# 02_Top_Level.net
KiCad netlist of a schematic drawn in Altium Designer
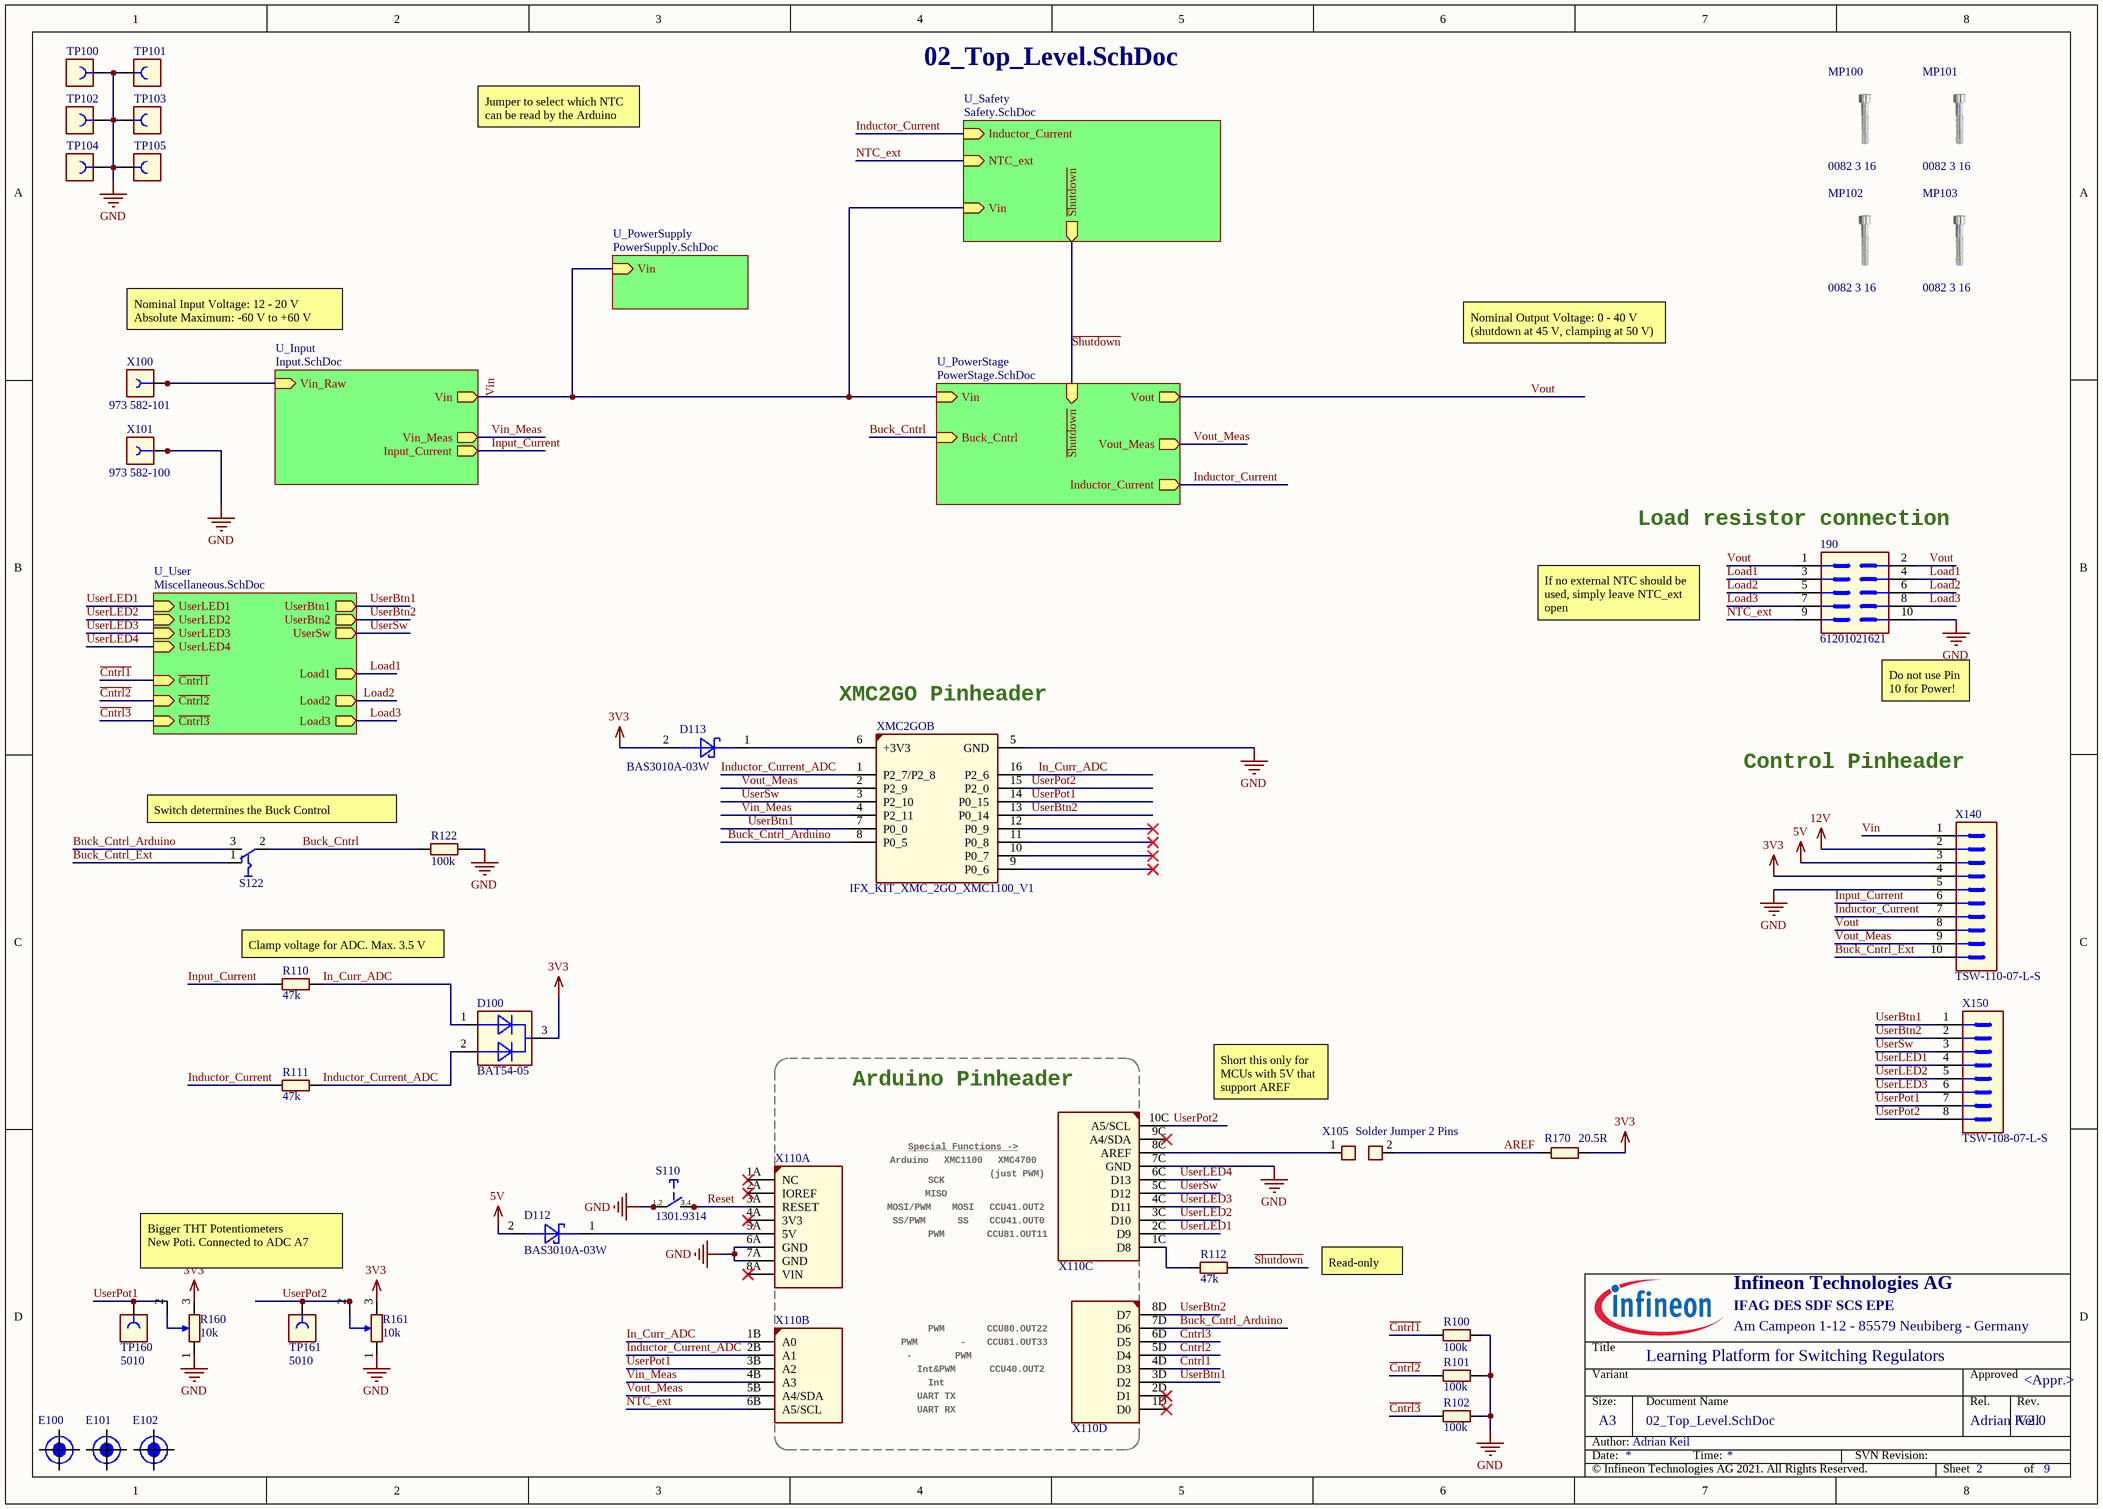
[diagram p0: 02_Top_Level.SchDoc]

(export (version "E")
  (design (tool "Eeschema 10.0.6"))
  (components
    (comp (ref "190")
      (value "61201021621")
      (footprint "CON-M-THT-61201021621")
      (description "WR-BHD Male Box Header, 2.54mm pitch, 10 pin, Vertical, Double row")
      (fields (field (name "MANUFACTURER") "Wurth Elektronik"))
      (libsource (lib "PCBLibraryData") (part "Header 5X2"))
    )
    (comp (ref "D100")
      (value "BAT54-05")
      (footprint "SOT95P240X110-3N-1-V")
      (description "Silicon Schottky Diode, LS(nH) 1.8, VR 30V")
      (fields
        (field (name "LEGACY PARTNUMBER") "IFX01401370")
        (field (name "MANUFACTURER") "Infineon Technologies")
      )
      (libsource (lib "PCBLibraryData") (part "d_dual_a1a2c3_3p"))
    )
    (comp (ref "D112")
      (value "BAS3010A-03W")
      (footprint "SOD2513X110N")
      (description "Medium Power AF Schottky Diode")
      (fields
        (field (name "LEGACY PARTNUMBER") "IFX01400145")
        (field (name "MANUFACTURER") "Infineon Technologies")
      )
      (libsource (lib "PCBLibraryData") (part "d_schottky_a"))
    )
    (comp (ref "D113")
      (value "BAS3010A-03W")
      (footprint "SOD2513X110N")
      (description "Medium Power AF Schottky Diode")
      (fields
        (field (name "LEGACY PARTNUMBER") "IFX01400145")
        (field (name "MANUFACTURER") "Infineon Technologies")
      )
      (libsource (lib "PCBLibraryData") (part "d_schottky_a"))
    )
    (comp (ref "E100")
      (value "~")
      (footprint "fiducial")
      (description "Fiducial Mark")
      (fields
        (field (name "LEGACY PARTNUMBER") "MEC10000008")
        (field (name "MANUFACTURER") "Infineon Technologies")
      )
      (libsource (lib "PCBLibraryData") (part "fiducial"))
    )
    (comp (ref "E101")
      (value "~")
      (footprint "fiducial")
      (description "Fiducial Mark")
      (fields
        (field (name "LEGACY PARTNUMBER") "MEC10000008")
        (field (name "MANUFACTURER") "Infineon Technologies")
      )
      (libsource (lib "PCBLibraryData") (part "fiducial"))
    )
    (comp (ref "E102")
      (value "~")
      (footprint "fiducial")
      (description "Fiducial Mark")
      (fields
        (field (name "LEGACY PARTNUMBER") "MEC10000008")
        (field (name "MANUFACTURER") "Infineon Technologies")
      )
      (libsource (lib "PCBLibraryData") (part "fiducial"))
    )
    (comp (ref "MP100")
      (value "0082 3 16")
      (footprint "SCREW_0082 3 16_NPTH")
      (description "Cheese Head Screw With Hexagon Socket, DIN 912 (ISO 4762), M3, 16mm length")
      (fields
        (field (name "LEGACY PARTNUMBER") "MEC10000167")
        (field (name "MANUFACTURER") "Wurth Elektronik")
      )
      (libsource (lib "PCBLibraryData") (part "Screw_0082 3 16"))
    )
    (comp (ref "MP101")
      (value "0082 3 16")
      (footprint "SCREW_0082 3 16_NPTH")
      (description "Cheese Head Screw With Hexagon Socket, DIN 912 (ISO 4762), M3, 16mm length")
      (fields
        (field (name "LEGACY PARTNUMBER") "MEC10000167")
        (field (name "MANUFACTURER") "Wurth Elektronik")
      )
      (libsource (lib "PCBLibraryData") (part "Screw_0082 3 16"))
    )
    (comp (ref "MP102")
      (value "0082 3 16")
      (footprint "SCREW_0082 3 16_NPTH")
      (description "Cheese Head Screw With Hexagon Socket, DIN 912 (ISO 4762), M3, 16mm length")
      (fields
        (field (name "LEGACY PARTNUMBER") "MEC10000167")
        (field (name "MANUFACTURER") "Wurth Elektronik")
      )
      (libsource (lib "PCBLibraryData") (part "Screw_0082 3 16"))
    )
    (comp (ref "MP103")
      (value "0082 3 16")
      (footprint "SCREW_0082 3 16_NPTH")
      (description "Cheese Head Screw With Hexagon Socket, DIN 912 (ISO 4762), M3, 16mm length")
      (fields
        (field (name "LEGACY PARTNUMBER") "MEC10000167")
        (field (name "MANUFACTURER") "Wurth Elektronik")
      )
      (libsource (lib "PCBLibraryData") (part "Screw_0082 3 16"))
    )
    (comp (ref "R100")
      (value "100k")
      (footprint "RESC3216X60N")
      (description "RES / STD / 100k / 250mW / 1% / 100ppm/K / -55°C to 155°C / 1206(3216) / SMD / -")
      (fields (field (name "LEGACY PARTNUMBER") "RES01802971") (field (name "MANUFACTURER") "Vishay"))
      (libsource (lib "") (part "RES-SGL-STD-02P_00000006_1"))
    )
    (comp (ref "R101")
      (value "100k")
      (footprint "RESC3216X60N")
      (description "RES / STD / 100k / 250mW / 1% / 100ppm/K / -55°C to 155°C / 1206(3216) / SMD / -")
      (fields (field (name "LEGACY PARTNUMBER") "RES01802971") (field (name "MANUFACTURER") "Vishay"))
      (libsource (lib "") (part "RES-SGL-STD-02P_00000006_1"))
    )
    (comp (ref "R102")
      (value "100k")
      (footprint "RESC3216X60N")
      (description "RES / STD / 100k / 250mW / 1% / 100ppm/K / -55°C to 155°C / 1206(3216) / SMD / -")
      (fields (field (name "LEGACY PARTNUMBER") "RES01802971") (field (name "MANUFACTURER") "Vishay"))
      (libsource (lib "") (part "RES-SGL-STD-02P_00000006_1"))
    )
    (comp (ref "R110")
      (value "47k")
      (footprint "RESC3216X60N")
      (description "RES / STD / 47k / 250mW / 1% / 100ppm/K / -55°C to 155°C / 1206(3216) / SMD / -")
      (fields (field (name "LEGACY PARTNUMBER") "RES01802933") (field (name "MANUFACTURER") "Vishay"))
      (libsource (lib "PCBLibraryData") (part "RES-SGL-STD-02P_00000006"))
    )
    (comp (ref "R111")
      (value "47k")
      (footprint "RESC3216X60N")
      (description "RES / STD / 47k / 250mW / 1% / 100ppm/K / -55°C to 155°C / 1206(3216) / SMD / -")
      (fields (field (name "LEGACY PARTNUMBER") "RES01802933") (field (name "MANUFACTURER") "Vishay"))
      (libsource (lib "PCBLibraryData") (part "RES-SGL-STD-02P_00000006"))
    )
    (comp (ref "R112")
      (value "47k")
      (footprint "RESC3216X60N")
      (description "RES / STD / 47k / 250mW / 1% / 100ppm/K / -55°C to 155°C / 1206(3216) / SMD / -")
      (fields (field (name "LEGACY PARTNUMBER") "RES01802933") (field (name "MANUFACTURER") "Vishay"))
      (libsource (lib "PCBLibraryData") (part "RES-SGL-STD-02P_00000006"))
    )
    (comp (ref "R122")
      (value "100k")
      (footprint "RESC3216X60N")
      (description "RES / STD / 100k / 250mW / 1% / 100ppm/K / -55°C to 155°C / 1206(3216) / SMD / -")
      (fields (field (name "LEGACY PARTNUMBER") "RES01802971") (field (name "MANUFACTURER") "Vishay"))
      (libsource (lib "") (part "RES-SGL-STD-02P_00000006_1"))
    )
    (comp (ref "R160")
      (value "10k")
      (footprint "POT-THT-3362P")
      (fields (field (name "MANUFACTURER") "Bourns"))
      (libsource (lib "PCBLibraryData") (part "RES-SGL-VAR-03P_00000026"))
    )
    (comp (ref "R161")
      (value "10k")
      (footprint "POT-THT-3362P")
      (fields (field (name "MANUFACTURER") "Bourns"))
      (libsource (lib "PCBLibraryData") (part "RES-SGL-VAR-03P_00000026"))
    )
    (comp (ref "R170")
      (value "20.5R")
      (footprint "RESC3216X60N")
      (description "RES / STD / 20.5R / 250mW / 1% / 100ppm/K / -55°C to 155°C / 1206(3216) / SMD / -")
      (fields (field (name "LEGACY PARTNUMBER") "RES01802548") (field (name "MANUFACTURER") "Vishay"))
      (libsource (lib "") (part "RES-SGL-STD-02P_00000006_1"))
    )
    (comp (ref "S110")
      (value "1301.9314")
      (footprint "SW-SMD-1301.9314")
      (description "Pushbutton Tactile Switch, Single Pole Single Throw, 4 Pins")
      (fields (field (name "LEGACY PARTNUMBER") "CON01500305") (field (name "MANUFACTURER") "Schurter"))
      (libsource (lib "PCBLibraryData") (part "sw_sr_no12_34_4p"))
    )
    (comp (ref "S122")
      (value "CL-SB-12A-01T")
      (footprint "SW-SMD-CL-SB-12A-01T")
      (description "Slid Switch, 12V, 200mA")
      (fields (field (name "MANUFACTURER") "NIDEC COPAL ELECTRONICS, Inc."))
      (libsource (lib "PCBLibraryData") (part "sw_co213_3p"))
    )
    (comp (ref "TP100")
      (value "5011")
      (footprint "CON-THT-TP-5011")
      (description "PC Test Point-Multipurpose THT, Black")
      (fields
        (field (name "LEGACY PARTNUMBER") "CON01500530")
        (field (name "MANUFACTURER") "Keystone Electronics Corp.")
      )
      (libsource (lib "PCBLibraryData") (part "connector_1_f"))
    )
    (comp (ref "TP101")
      (value "5011")
      (footprint "CON-THT-TP-5011")
      (description "PC Test Point-Multipurpose THT, Black")
      (fields
        (field (name "LEGACY PARTNUMBER") "CON01500530")
        (field (name "MANUFACTURER") "Keystone Electronics Corp.")
      )
      (libsource (lib "") (part "connector_1_f_2"))
    )
    (comp (ref "TP102")
      (value "5011")
      (footprint "CON-THT-TP-5011")
      (description "PC Test Point-Multipurpose THT, Black")
      (fields
        (field (name "LEGACY PARTNUMBER") "CON01500530")
        (field (name "MANUFACTURER") "Keystone Electronics Corp.")
      )
      (libsource (lib "PCBLibraryData") (part "connector_1_f"))
    )
    (comp (ref "TP103")
      (value "5011")
      (footprint "CON-THT-TP-5011")
      (description "PC Test Point-Multipurpose THT, Black")
      (fields
        (field (name "LEGACY PARTNUMBER") "CON01500530")
        (field (name "MANUFACTURER") "Keystone Electronics Corp.")
      )
      (libsource (lib "") (part "connector_1_f_2"))
    )
    (comp (ref "TP104")
      (value "5011")
      (footprint "CON-THT-TP-5011")
      (description "PC Test Point-Multipurpose THT, Black")
      (fields
        (field (name "LEGACY PARTNUMBER") "CON01500530")
        (field (name "MANUFACTURER") "Keystone Electronics Corp.")
      )
      (libsource (lib "PCBLibraryData") (part "connector_1_f"))
    )
    (comp (ref "TP105")
      (value "5011")
      (footprint "CON-THT-TP-5011")
      (description "PC Test Point-Multipurpose THT, Black")
      (fields
        (field (name "LEGACY PARTNUMBER") "CON01500530")
        (field (name "MANUFACTURER") "Keystone Electronics Corp.")
      )
      (libsource (lib "") (part "connector_1_f_2"))
    )
    (comp (ref "TP160")
      (value "5010")
      (footprint "CON-THT-TP-5010")
      (description "PC Test Point-Multipurpose THT, Red")
      (fields
        (field (name "LEGACY PARTNUMBER") "CON01500529")
        (field (name "MANUFACTURER") "Keystone Electronics Corp.")
      )
      (libsource (lib "") (part "connector_1_f_1"))
    )
    (comp (ref "TP161")
      (value "5010")
      (footprint "CON-THT-TP-5010")
      (description "PC Test Point-Multipurpose THT, Red")
      (fields
        (field (name "LEGACY PARTNUMBER") "CON01500529")
        (field (name "MANUFACTURER") "Keystone Electronics Corp.")
      )
      (libsource (lib "") (part "connector_1_f_1"))
    )
    (comp (ref "X100")
      (value "973 582-101")
      (footprint "CON-THT-973 582- 101")
      (description "Banana Socket, Red, 17.5mm Pitch")
      (fields
        (field (name "LEGACY PARTNUMBER") "CON01500041")
        (field (name "MANUFACTURER") "Hirschmann Test & Measurement")
      )
      (libsource (lib "PCBLibraryData") (part "soc_banana_2p"))
    )
    (comp (ref "X101")
      (value "973 582-100")
      (footprint "CON-THT-973 582- 100")
      (description "Banana Socket, black, 17.5mm Pitch")
      (fields
        (field (name "LEGACY PARTNUMBER") "CON01500045")
        (field (name "MANUFACTURER") "Hirschmann Test & Measurement")
      )
      (libsource (lib "PCBLibraryData") (part "soc_banana_2p"))
    )
    (comp (ref "X105")
      (value "Solder Jumper 2 Pins")
      (footprint "SOLDER_BRIDGE_0.7X1.299PAD")
      (fields
        (field (name "LEGACY PARTNUMBER") "CON01500959")
        (field (name "MANUFACTURER") "Infineon Technologies")
      )
      (libsource (lib "PCBLibraryData") (part "SJP_2P"))
    )
    (comp (ref "X110")
      (value "Arduino-Uno")
      (footprint "Arduino-Uno")
      (description "Arduino Uno is a microcontroller board based on the ATmega328P")
      (fields (field (name "MANUFACTURER") "Infineon Technologies"))
      (libsource (lib "") (part "Arduino-Uno_1"))
    )
    (comp (ref "X140")
      (value "TSW-110-07-L-S")
      (footprint "CON-M-THT-TSW-110-07-L-S")
      (description "Through hole .025 SQ Post Header, 2.54mm pitch, 10 pin, vertical, single row")
      (fields (field (name "LEGACY PARTNUMBER") "CON01500578") (field (name "MANUFACTURER") "Samtec"))
      (libsource (lib "PCBLibraryData") (part "Header 10"))
    )
    (comp (ref "X150")
      (value "TSW-108-07-L-S")
      (footprint "CON-M-THT-TSW-108-07-L-S")
      (description "Through hole .025 SQ Post Header, 2.54mm pitch, 8 pin, vertical, single row")
      (fields (field (name "LEGACY PARTNUMBER") "CON01500577") (field (name "MANUFACTURER") "Samtec"))
      (libsource (lib "PCBLibraryData") (part "Header 8"))
    )
    (comp (ref "XMC2GO")
      (value "IFX_KIT_XMC_2GO_XMC1100_V1")
      (footprint "IFX-THT-KIT_XMC_2GO_XMC1100_V1")
      (description "Evaluation Board For XMC1000 Family, The XMC 2Go, 16 Pins+5 Pins")
      (fields (field (name "MANUFACTURER") "Infineon Technologies"))
      (libsource (lib "PCBLibraryData") (part "KIT_XMC_2GO_XMC1100_V1"))
    )
  )
  (nets
    (net (code "1") (name "/AREF") (class "Default")
      (node (ref "R170") (pin "1") (pinfunction "1_1") (pintype "passive"))
      (node (ref "X105") (pin "2") (pinfunction "2_2") (pintype "passive"))
    )
    (net (code "2") (name "/Buck_Cntrl") (class "Default")
      (node (ref "R122") (pin "1") (pinfunction "1_1") (pintype "passive"))
      (node (ref "S122") (pin "2") (pinfunction "2_2") (pintype "passive"))
    )
    (net (code "3") (name "/Buck_Cntrl_Arduino") (class "Default")
      (node (ref "S122") (pin "3") (pinfunction "3_3") (pintype "passive"))
      (node (ref "X110") (pin "7D") (pinfunction "D6_7D") (pintype "passive"))
      (node (ref "XMC2GO") (pin "8") (pinfunction "P0_5_8") (pintype "passive"))
    )
    (net (code "4") (name "/Buck_Cntrl_Ext") (class "Default")
      (node (ref "S122") (pin "1") (pinfunction "1_1") (pintype "passive"))
      (node (ref "X140") (pin "10") (pinfunction "10_10") (pintype "passive"))
    )
    (net (code "5") (name "/Cntrl1") (class "Default")
      (node (ref "R100") (pin "1") (pinfunction "1_1") (pintype "passive"))
      (node (ref "X110") (pin "4D") (pinfunction "D3_4D") (pintype "passive"))
    )
    (net (code "6") (name "/Cntrl2") (class "Default")
      (node (ref "R101") (pin "1") (pinfunction "1_1") (pintype "passive"))
      (node (ref "X110") (pin "5D") (pinfunction "D4_5D") (pintype "passive"))
    )
    (net (code "7") (name "/Cntrl3") (class "Default")
      (node (ref "R102") (pin "1") (pinfunction "1_1") (pintype "passive"))
      (node (ref "X110") (pin "6D") (pinfunction "D5_6D") (pintype "passive"))
    )
    (net (code "8") (name "/In_Curr_ADC") (class "Default")
      (node (ref "D100") (pin "1") (pinfunction "ANODE_1_1") (pintype "passive"))
      (node (ref "R110") (pin "1") (pinfunction "1_1") (pintype "passive"))
      (node (ref "X110") (pin "1B") (pinfunction "A0_1B") (pintype "passive"))
      (node (ref "XMC2GO") (pin "16") (pinfunction "P2_6_16") (pintype "passive"))
    )
    (net (code "9") (name "/Inductor_Current") (class "Default")
      (node (ref "R111") (pin "2") (pinfunction "2_2") (pintype "passive"))
      (node (ref "X140") (pin "7") (pinfunction "7_7") (pintype "passive"))
    )
    (net (code "10") (name "/Inductor_Current_ADC") (class "Default")
      (node (ref "D100") (pin "2") (pinfunction "ANODE_2_2") (pintype "passive"))
      (node (ref "R111") (pin "1") (pinfunction "1_1") (pintype "passive"))
      (node (ref "X110") (pin "2B") (pinfunction "A1_2B") (pintype "passive"))
      (node (ref "XMC2GO") (pin "1") (pinfunction "P2_7/P2_8_1") (pintype "passive"))
    )
    (net (code "11") (name "/Input_Current") (class "Default")
      (node (ref "R110") (pin "2") (pinfunction "2_2") (pintype "passive"))
      (node (ref "X140") (pin "6") (pinfunction "6_6") (pintype "passive"))
    )
    (net (code "12") (name "/Load1") (class "Default")
      (node (ref "190") (pin "3") (pinfunction "3_3") (pintype "passive"))
      (node (ref "190") (pin "4") (pinfunction "4_4") (pintype "passive"))
    )
    (net (code "13") (name "/Load2") (class "Default")
      (node (ref "190") (pin "5") (pinfunction "5_5") (pintype "passive"))
      (node (ref "190") (pin "6") (pinfunction "6_6") (pintype "passive"))
    )
    (net (code "14") (name "/Load3") (class "Default")
      (node (ref "190") (pin "7") (pinfunction "7_7") (pintype "passive"))
      (node (ref "190") (pin "8") (pinfunction "8_8") (pintype "passive"))
    )
    (net (code "15") (name "/NTC_ext") (class "Default")
      (node (ref "190") (pin "9") (pinfunction "9_9") (pintype "passive"))
      (node (ref "X110") (pin "6B") (pinfunction "A5/SCL_6B") (pintype "passive"))
    )
    (net (code "16") (name "/Reset") (class "Default")
      (node (ref "S110") (pin "3") (pinfunction "3_3") (pintype "passive"))
      (node (ref "S110") (pin "4") (pinfunction "4_4") (pintype "passive"))
      (node (ref "X110") (pin "3A") (pinfunction "RESET_3A") (pintype "passive"))
    )
    (net (code "17") (name "/Shutdown") (class "Default")
      (node (ref "R112") (pin "1") (pinfunction "1_1") (pintype "passive"))
    )
    (net (code "18") (name "/UserBtn1") (class "Default")
      (node (ref "X110") (pin "3D") (pinfunction "D2_3D") (pintype "passive"))
      (node (ref "X150") (pin "1") (pinfunction "1_1") (pintype "passive"))
      (node (ref "XMC2GO") (pin "7") (pinfunction "P0_0_7") (pintype "passive"))
    )
    (net (code "19") (name "/UserBtn2") (class "Default")
      (node (ref "X110") (pin "8D") (pinfunction "D7_8D") (pintype "passive"))
      (node (ref "X150") (pin "2") (pinfunction "2_2") (pintype "passive"))
      (node (ref "XMC2GO") (pin "13") (pinfunction "P0_14_13") (pintype "passive"))
    )
    (net (code "20") (name "/UserLED1") (class "Default")
      (node (ref "X110") (pin "2C") (pinfunction "D9_2C") (pintype "passive"))
      (node (ref "X150") (pin "4") (pinfunction "4_4") (pintype "passive"))
    )
    (net (code "21") (name "/UserLED2") (class "Default")
      (node (ref "X110") (pin "3C") (pinfunction "D10_3C") (pintype "passive"))
      (node (ref "X150") (pin "5") (pinfunction "5_5") (pintype "passive"))
    )
    (net (code "22") (name "/UserLED3") (class "Default")
      (node (ref "X110") (pin "4C") (pinfunction "D11_4C") (pintype "passive"))
      (node (ref "X150") (pin "6") (pinfunction "6_6") (pintype "passive"))
    )
    (net (code "23") (name "/UserLED4") (class "Default")
      (node (ref "X110") (pin "6C") (pinfunction "D13_6C") (pintype "passive"))
    )
    (net (code "24") (name "/UserPot1") (class "Default")
      (node (ref "R160") (pin "2") (pinfunction "2_2") (pintype "passive"))
      (node (ref "TP160") (pin "1") (pinfunction "1_1") (pintype "passive"))
      (node (ref "X110") (pin "3B") (pinfunction "A2_3B") (pintype "passive"))
      (node (ref "X150") (pin "7") (pinfunction "7_7") (pintype "passive"))
      (node (ref "XMC2GO") (pin "14") (pinfunction "P0_15_14") (pintype "passive"))
    )
    (net (code "25") (name "/UserPot2") (class "Default")
      (node (ref "R161") (pin "2") (pinfunction "2_2") (pintype "passive"))
      (node (ref "TP161") (pin "1") (pinfunction "1_1") (pintype "passive"))
      (node (ref "X110") (pin "10C") (pinfunction "A5/SCL_10C") (pintype "passive"))
      (node (ref "X150") (pin "8") (pinfunction "8_8") (pintype "passive"))
      (node (ref "XMC2GO") (pin "15") (pinfunction "P2_0_15") (pintype "passive"))
    )
    (net (code "26") (name "/UserSw") (class "Default")
      (node (ref "X110") (pin "5C") (pinfunction "D12_5C") (pintype "passive"))
      (node (ref "X150") (pin "3") (pinfunction "3_3") (pintype "passive"))
      (node (ref "XMC2GO") (pin "3") (pinfunction "P2_10_3") (pintype "passive"))
    )
    (net (code "27") (name "/Vin") (class "Default")
      (node (ref "X140") (pin "1") (pinfunction "1_1") (pintype "passive"))
    )
    (net (code "28") (name "/Vin_Meas") (class "Default")
      (node (ref "X110") (pin "4B") (pinfunction "A3_4B") (pintype "passive"))
      (node (ref "XMC2GO") (pin "4") (pinfunction "P2_11_4") (pintype "passive"))
    )
    (net (code "29") (name "/Vin_Raw") (class "Default")
      (node (ref "X100") (pin "1") (pinfunction "1_1") (pintype "passive"))
      (node (ref "X100") (pin "2") (pinfunction "2_2") (pintype "passive"))
    )
    (net (code "30") (name "/Vout") (class "Default")
      (node (ref "190") (pin "1") (pinfunction "1_1") (pintype "passive"))
      (node (ref "190") (pin "2") (pinfunction "2_2") (pintype "passive"))
      (node (ref "X140") (pin "8") (pinfunction "8_8") (pintype "passive"))
    )
    (net (code "31") (name "/Vout_Meas") (class "Default")
      (node (ref "X110") (pin "5B") (pinfunction "A4/SDA_5B") (pintype "passive"))
      (node (ref "X140") (pin "9") (pinfunction "9_9") (pintype "passive"))
      (node (ref "XMC2GO") (pin "2") (pinfunction "P2_9_2") (pintype "passive"))
    )
    (net (code "32") (name "3V3") (class "Default")
      (node (ref "D100") (pin "3") (pinfunction "CATHODE_3") (pintype "passive"))
      (node (ref "D113") (pin "2") (pinfunction "Anode_2") (pintype "passive"))
      (node (ref "R160") (pin "3") (pinfunction "3_3") (pintype "passive"))
      (node (ref "R161") (pin "3") (pinfunction "3_3") (pintype "passive"))
      (node (ref "R170") (pin "2") (pinfunction "2_2") (pintype "passive"))
      (node (ref "X140") (pin "4") (pinfunction "4_4") (pintype "passive"))
    )
    (net (code "33") (name "5V") (class "Default")
      (node (ref "D112") (pin "2") (pinfunction "Anode_2") (pintype "passive"))
      (node (ref "X140") (pin "3") (pinfunction "3_3") (pintype "passive"))
    )
    (net (code "34") (name "12V") (class "Default")
      (node (ref "X140") (pin "2") (pinfunction "2_2") (pintype "passive"))
    )
    (net (code "35") (name "GND") (class "Default")
      (node (ref "190") (pin "10") (pinfunction "10_10") (pintype "passive"))
      (node (ref "R100") (pin "2") (pinfunction "2_2") (pintype "passive"))
      (node (ref "R101") (pin "2") (pinfunction "2_2") (pintype "passive"))
      (node (ref "R102") (pin "2") (pinfunction "2_2") (pintype "passive"))
      (node (ref "R122") (pin "2") (pinfunction "2_2") (pintype "passive"))
      (node (ref "R160") (pin "1") (pinfunction "1_1") (pintype "passive"))
      (node (ref "R161") (pin "1") (pinfunction "1_1") (pintype "passive"))
      (node (ref "S110") (pin "1") (pinfunction "1_1") (pintype "passive"))
      (node (ref "S110") (pin "2") (pinfunction "2_2") (pintype "passive"))
      (node (ref "TP100") (pin "1") (pinfunction "1_1") (pintype "passive"))
      (node (ref "TP101") (pin "1") (pinfunction "1_1") (pintype "passive"))
      (node (ref "TP102") (pin "1") (pinfunction "1_1") (pintype "passive"))
      (node (ref "TP103") (pin "1") (pinfunction "1_1") (pintype "passive"))
      (node (ref "TP104") (pin "1") (pinfunction "1_1") (pintype "passive"))
      (node (ref "TP105") (pin "1") (pinfunction "1_1") (pintype "passive"))
      (node (ref "X101") (pin "1") (pinfunction "1_1") (pintype "passive"))
      (node (ref "X101") (pin "2") (pinfunction "2_2") (pintype "passive"))
      (node (ref "X110") (pin "6A") (pinfunction "GND_6A") (pintype "passive"))
      (node (ref "X110") (pin "7A") (pinfunction "GND_7A") (pintype "passive"))
      (node (ref "X110") (pin "7C") (pinfunction "GND_7C") (pintype "passive"))
      (node (ref "X140") (pin "5") (pinfunction "5_5") (pintype "passive"))
      (node (ref "XMC2GO") (pin "5") (pinfunction "GND_5") (pintype "power_in"))
    )
    (net (code "36") (name "Net-(D112-Cathode)") (class "Default")
      (node (ref "D112") (pin "1") (pinfunction "Cathode_1") (pintype "passive"))
      (node (ref "X110") (pin "5A") (pinfunction "5V_5A") (pintype "passive"))
    )
    (net (code "37") (name "Net-(D113-Cathode)") (class "Default")
      (node (ref "D113") (pin "1") (pinfunction "Cathode_1") (pintype "passive"))
      (node (ref "XMC2GO") (pin "6") (pinfunction "+3V3_6") (pintype "power_in"))
    )
    (net (code "38") (name "Net-(X110C-AREF)") (class "Default")
      (node (ref "X105") (pin "1") (pinfunction "1_1") (pintype "passive"))
      (node (ref "X110") (pin "8C") (pinfunction "AREF_8C") (pintype "passive"))
    )
    (net (code "39") (name "Net-(X110C-D8)") (class "Default")
      (node (ref "R112") (pin "2") (pinfunction "2_2") (pintype "passive"))
      (node (ref "X110") (pin "1C") (pinfunction "D8_1C") (pintype "passive"))
    )
    (net (code "40") (name "unconnected-(E100-Pad1)") (class "Default")
      (node (ref "E100") (pin "1") (pinfunction "1_1") (pintype "passive"))
    )
    (net (code "41") (name "unconnected-(E101-Pad1)") (class "Default")
      (node (ref "E101") (pin "1") (pinfunction "1_1") (pintype "passive"))
    )
    (net (code "42") (name "unconnected-(E102-Pad1)") (class "Default")
      (node (ref "E102") (pin "1") (pinfunction "1_1") (pintype "passive"))
    )
    (net (code "43") (name "unconnected-(X110A-3V3-Pad4A)") (class "Default")
      (node (ref "X110") (pin "4A") (pinfunction "3V3_4A") (pintype "passive+no_connect"))
    )
    (net (code "44") (name "unconnected-(X110A-IOREF-Pad2A)") (class "Default")
      (node (ref "X110") (pin "2A") (pinfunction "IOREF_2A") (pintype "passive+no_connect"))
    )
    (net (code "45") (name "unconnected-(X110A-NC-Pad1A)") (class "Default")
      (node (ref "X110") (pin "1A") (pinfunction "NC_1A") (pintype "passive+no_connect"))
    )
    (net (code "46") (name "unconnected-(X110A-VIN-Pad8A)") (class "Default")
      (node (ref "X110") (pin "8A") (pinfunction "VIN_8A") (pintype "passive+no_connect"))
    )
    (net (code "47") (name "unconnected-(X110C-A4{slash}SDA-Pad9C)") (class "Default")
      (node (ref "X110") (pin "9C") (pinfunction "A4/SDA_9C") (pintype "passive+no_connect"))
    )
    (net (code "48") (name "unconnected-(X110D-D0-Pad1D)") (class "Default")
      (node (ref "X110") (pin "1D") (pinfunction "D0_1D") (pintype "passive+no_connect"))
    )
    (net (code "49") (name "unconnected-(X110D-D1-Pad2D)") (class "Default")
      (node (ref "X110") (pin "2D") (pinfunction "D1_2D") (pintype "passive+no_connect"))
    )
    (net (code "50") (name "unconnected-(XMC2GOB-P0_6-Pad9)") (class "Default")
      (node (ref "XMC2GO") (pin "9") (pinfunction "P0_6_9") (pintype "passive+no_connect"))
    )
    (net (code "51") (name "unconnected-(XMC2GOB-P0_7-Pad10)") (class "Default")
      (node (ref "XMC2GO") (pin "10") (pinfunction "P0_7_10") (pintype "passive+no_connect"))
    )
    (net (code "52") (name "unconnected-(XMC2GOB-P0_8-Pad11)") (class "Default")
      (node (ref "XMC2GO") (pin "11") (pinfunction "P0_8_11") (pintype "passive+no_connect"))
    )
    (net (code "53") (name "unconnected-(XMC2GOB-P0_9-Pad12)") (class "Default")
      (node (ref "XMC2GO") (pin "12") (pinfunction "P0_9_12") (pintype "passive+no_connect"))
    )
  )
)
